# RadioBridge.net
KiCad netlist of a schematic drawn in EAGLE
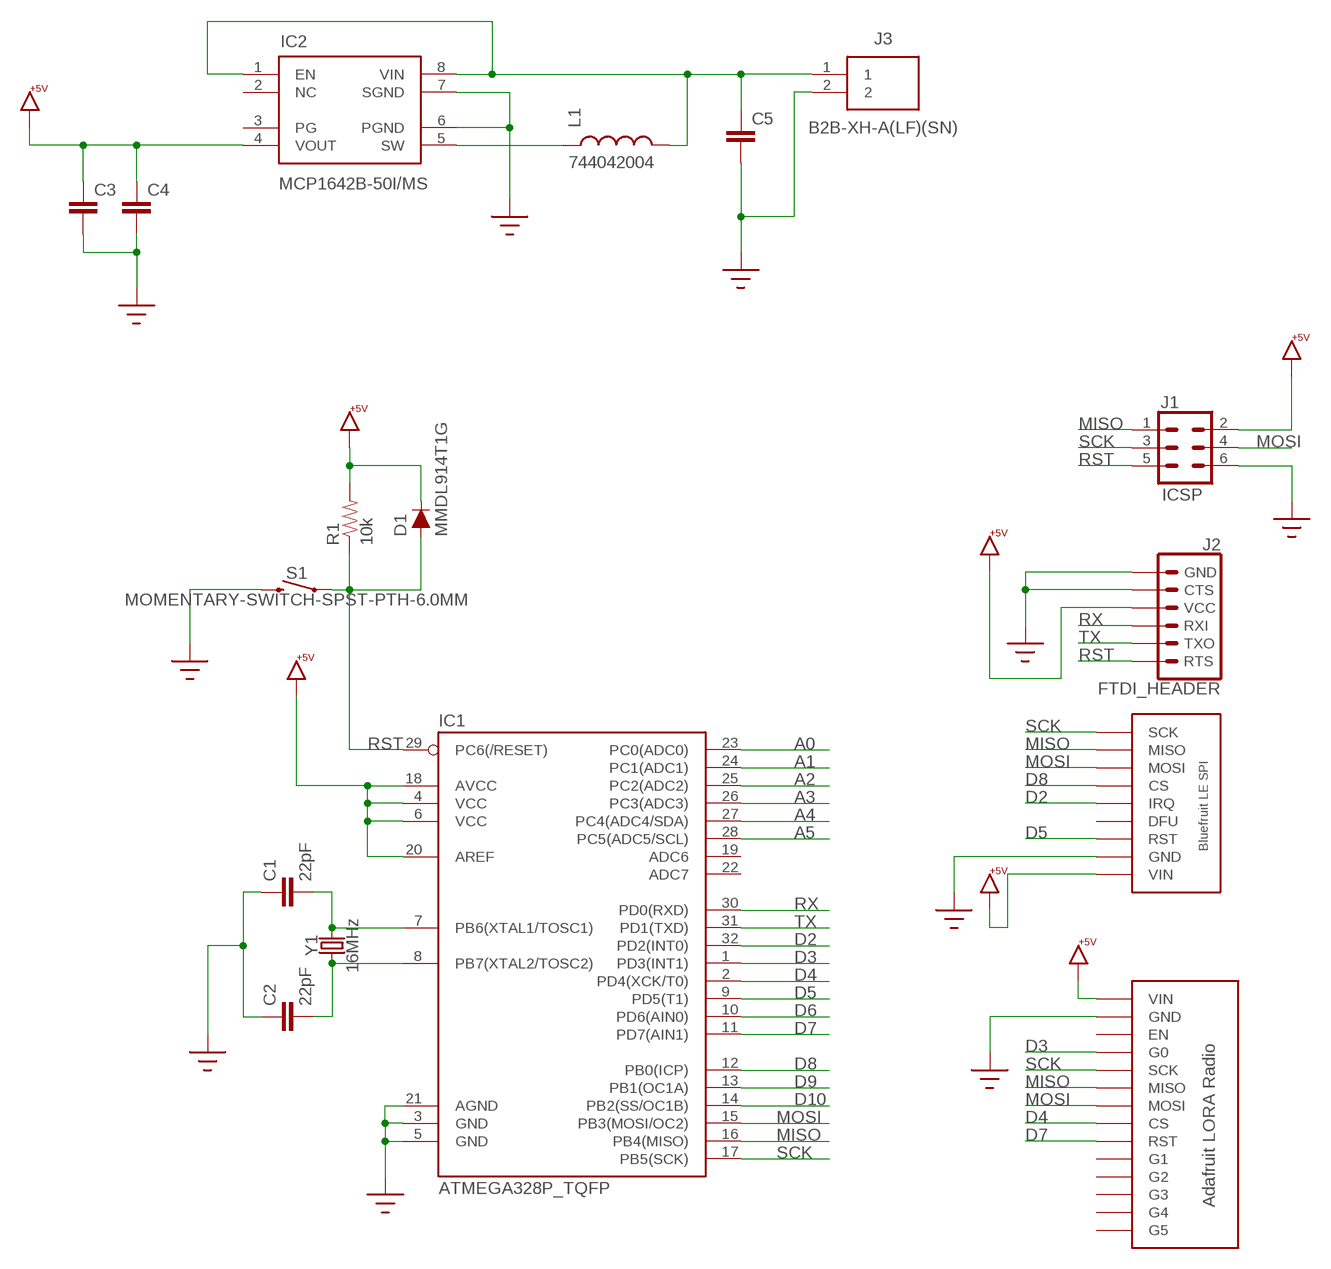
[diagram p0: schematic, sheet 1]

(export (version "E")
  (design (tool "Eeschema 10.0.6"))
  (components
    (comp (ref "C1")
      (value "22pF")
      (footprint "eagle-import:0603-CAP")
      (libsource (lib "eagle-import") (part "CAP0603-CAP"))
    )
    (comp (ref "C2")
      (value "22pF")
      (footprint "eagle-import:0603-CAP")
      (libsource (lib "eagle-import") (part "CAP0603-CAP"))
    )
    (comp (ref "C3")
      (value "CAP0805")
      (footprint "eagle-import:0805")
      (libsource (lib "eagle-import") (part "CAP0805"))
    )
    (comp (ref "C4")
      (value "CAP0805")
      (footprint "eagle-import:0805")
      (libsource (lib "eagle-import") (part "CAP0805"))
    )
    (comp (ref "C5")
      (value "CAP0805")
      (footprint "eagle-import:0805")
      (libsource (lib "eagle-import") (part "CAP0805"))
    )
    (comp (ref "D1")
      (value "MMDL914T1G")
      (footprint "eagle-import:SOD-323")
      (libsource (lib "eagle-import") (part "DIODE-BAS16J"))
    )
    (comp (ref "IC1")
      (value "ATMEGA328P_TQFP")
      (footprint "eagle-import:TQFP32-08")
      (libsource (lib "eagle-import") (part "ATMEGA328P_TQFP"))
    )
    (comp (ref "IC2")
      (value "MCP1642B-50I/MS")
      (footprint "eagle-import:MSOP8")
      (libsource (lib "eagle-import") (part "MCP1642B-50I/MS"))
    )
    (comp (ref "J1")
      (value "ICSP")
      (footprint "eagle-import:2X3")
      (libsource (lib "eagle-import") (part "CONN_03X22X3_SILK_MALE_PTH"))
    )
    (comp (ref "J2")
      (value "FTDI_HEADER")
      (footprint "eagle-import:1X06_LOCK")
      (libsource (lib "eagle-import") (part "6_PIN_SERIAL_TARGETLOCK"))
    )
    (comp (ref "J3")
      (value "B2B-XH-A(LF)(SN)")
      (footprint "eagle-import:SHDR2W64P0X250_1X2_740X575X700")
      (fields (field (name "RS_PART_NUMBER") "8201554"))
      (libsource (lib "eagle-import") (part "B2B-XH-A(LF)(SN)"))
    )
    (comp (ref "L1")
      (value "744042004")
      (footprint "eagle-import:1919(4848_METRIC)")
      (libsource (lib "eagle-import") (part "INDUCTOR"))
    )
    (comp (ref "R1")
      (value "10k")
      (footprint "eagle-import:0603-RES")
      (libsource (lib "eagle-import") (part "RESISTOR0603-RES"))
    )
    (comp (ref "S1")
      (value "MOMENTARY-SWITCH-SPST-PTH-6.0MM")
      (footprint "eagle-import:TACTILE_SWITCH_PTH_6.0MM")
      (libsource (lib "eagle-import") (part "MOMENTARY-SWITCH-SPST-PTH-6.0MM"))
    )
    (comp (ref "U$1")
      (value "BLUEFRUIT_LE_FRIEND_SPI")
      (footprint "eagle-import:BLUEFRUIT_LE_FRIEND_SPI")
      (libsource (lib "eagle-import") (part "BLUEFRUIT_LE_FRIEND_SPI"))
    )
    (comp (ref "U$2")
      (value "ADAFRUIT_LORA_RADIO")
      (footprint "eagle-import:ADAFRUIT_LORA_RADIO")
      (libsource (lib "eagle-import") (part "ADAFRUIT_LORA_RADIO"))
    )
    (comp (ref "Y1")
      (value "16MHz")
      (footprint "eagle-import:CRYSTAL-SMD-5X3.2-4PAD")
      (libsource (lib "eagle-import") (part "CRYSTAL-16MHZSMD-5X3.2"))
    )
  )
  (nets
    (net (code "1") (name "+5V") (class "Default")
      (node (ref "C3") (pin "1") (pinfunction "1_1") (pintype "passive"))
      (node (ref "C4") (pin "1") (pinfunction "1_1") (pintype "passive"))
      (node (ref "D1") (pin "C") (pinfunction "C_C") (pintype "passive"))
      (node (ref "IC1") (pin "18") (pinfunction "AVCC_18") (pintype "bidirectional"))
      (node (ref "IC1") (pin "20") (pinfunction "AREF_20") (pintype "bidirectional"))
      (node (ref "IC1") (pin "4") (pinfunction "VCC_4") (pintype "bidirectional"))
      (node (ref "IC1") (pin "6") (pinfunction "VCC_6") (pintype "bidirectional"))
      (node (ref "IC2") (pin "4") (pinfunction "VOUT_4") (pintype "bidirectional"))
      (node (ref "J1") (pin "2") (pinfunction "2_2") (pintype "bidirectional"))
      (node (ref "J2") (pin "4") (pinfunction "VCC_4") (pintype "passive"))
      (node (ref "R1") (pin "2") (pinfunction "2_2") (pintype "passive"))
      (node (ref "U$1") (pin "P$9") (pinfunction "VIN_P$9") (pintype "bidirectional"))
      (node (ref "U$2") (pin "P$1") (pinfunction "VIN_P$1") (pintype "bidirectional"))
    )
    (net (code "2") (name "/A0") (class "Default")
      (node (ref "IC1") (pin "23") (pinfunction "PC0(ADC0)_23") (pintype "bidirectional"))
    )
    (net (code "3") (name "/A1") (class "Default")
      (node (ref "IC1") (pin "24") (pinfunction "PC1(ADC1)_24") (pintype "bidirectional"))
    )
    (net (code "4") (name "/A2") (class "Default")
      (node (ref "IC1") (pin "25") (pinfunction "PC2(ADC2)_25") (pintype "bidirectional"))
    )
    (net (code "5") (name "/A3") (class "Default")
      (node (ref "IC1") (pin "26") (pinfunction "PC3(ADC3)_26") (pintype "bidirectional"))
    )
    (net (code "6") (name "/A4") (class "Default")
      (node (ref "IC1") (pin "27") (pinfunction "PC4(ADC4/SDA)_27") (pintype "bidirectional"))
    )
    (net (code "7") (name "/A5") (class "Default")
      (node (ref "IC1") (pin "28") (pinfunction "PC5(ADC5/SCL)_28") (pintype "bidirectional"))
    )
    (net (code "8") (name "/D2") (class "Default")
      (node (ref "IC1") (pin "32") (pinfunction "PD2(INT0)_32") (pintype "bidirectional"))
      (node (ref "U$1") (pin "P$5") (pinfunction "IRQ_P$5") (pintype "bidirectional"))
    )
    (net (code "9") (name "/D3") (class "Default")
      (node (ref "IC1") (pin "1") (pinfunction "PD3(INT1)_1") (pintype "bidirectional"))
      (node (ref "U$2") (pin "P$4") (pinfunction "G0_P$4") (pintype "bidirectional"))
    )
    (net (code "10") (name "/D4") (class "Default")
      (node (ref "IC1") (pin "2") (pinfunction "PD4(XCK/T0)_2") (pintype "bidirectional"))
      (node (ref "U$2") (pin "P$8") (pinfunction "CS_P$8") (pintype "bidirectional"))
    )
    (net (code "11") (name "/D5") (class "Default")
      (node (ref "IC1") (pin "9") (pinfunction "PD5(T1)_9") (pintype "bidirectional"))
      (node (ref "U$1") (pin "P$7") (pinfunction "RST_P$7") (pintype "bidirectional"))
    )
    (net (code "12") (name "/D6") (class "Default")
      (node (ref "IC1") (pin "10") (pinfunction "PD6(AIN0)_10") (pintype "bidirectional"))
    )
    (net (code "13") (name "/D7") (class "Default")
      (node (ref "IC1") (pin "11") (pinfunction "PD7(AIN1)_11") (pintype "bidirectional"))
      (node (ref "U$2") (pin "P$9") (pinfunction "RST_P$9") (pintype "bidirectional"))
    )
    (net (code "14") (name "/D8") (class "Default")
      (node (ref "IC1") (pin "12") (pinfunction "PB0(ICP)_12") (pintype "bidirectional"))
      (node (ref "U$1") (pin "P$4") (pinfunction "CS_P$4") (pintype "bidirectional"))
    )
    (net (code "15") (name "/D9") (class "Default")
      (node (ref "IC1") (pin "13") (pinfunction "PB1(OC1A)_13") (pintype "bidirectional"))
    )
    (net (code "16") (name "/D10") (class "Default")
      (node (ref "IC1") (pin "14") (pinfunction "PB2(SS/OC1B)_14") (pintype "bidirectional"))
    )
    (net (code "17") (name "/MISO") (class "Default")
      (node (ref "IC1") (pin "16") (pinfunction "PB4(MISO)_16") (pintype "bidirectional"))
      (node (ref "J1") (pin "1") (pinfunction "1_1") (pintype "bidirectional"))
      (node (ref "U$1") (pin "P$2") (pinfunction "MISO_P$2") (pintype "bidirectional"))
      (node (ref "U$2") (pin "P$6") (pinfunction "MISO_P$6") (pintype "bidirectional"))
    )
    (net (code "18") (name "/MOSI") (class "Default")
      (node (ref "IC1") (pin "15") (pinfunction "PB3(MOSI/OC2)_15") (pintype "bidirectional"))
      (node (ref "J1") (pin "4") (pinfunction "4_4") (pintype "bidirectional"))
      (node (ref "U$1") (pin "P$3") (pinfunction "MOSI_P$3") (pintype "bidirectional"))
      (node (ref "U$2") (pin "P$7") (pinfunction "MOSI_P$7") (pintype "bidirectional"))
    )
    (net (code "19") (name "/RST") (class "Default")
      (node (ref "D1") (pin "A") (pinfunction "A_A") (pintype "passive"))
      (node (ref "IC1") (pin "29") (pinfunction "PC6(/RESET)_29") (pintype "bidirectional"))
      (node (ref "J1") (pin "5") (pinfunction "5_5") (pintype "bidirectional"))
      (node (ref "J2") (pin "1") (pinfunction "RTS_1") (pintype "passive"))
      (node (ref "R1") (pin "1") (pinfunction "1_1") (pintype "passive"))
      (node (ref "S1") (pin "1") (pinfunction "1_1") (pintype "passive"))
    )
    (net (code "20") (name "/RX") (class "Default")
      (node (ref "IC1") (pin "30") (pinfunction "PD0(RXD)_30") (pintype "bidirectional"))
      (node (ref "J2") (pin "3") (pinfunction "RXI_3") (pintype "passive"))
    )
    (net (code "21") (name "/SCK") (class "Default")
      (node (ref "IC1") (pin "17") (pinfunction "PB5(SCK)_17") (pintype "bidirectional"))
      (node (ref "J1") (pin "3") (pinfunction "3_3") (pintype "bidirectional"))
      (node (ref "U$1") (pin "P$1") (pinfunction "SCK_P$1") (pintype "bidirectional"))
      (node (ref "U$2") (pin "P$5") (pinfunction "SCK_P$5") (pintype "bidirectional"))
    )
    (net (code "22") (name "/TX") (class "Default")
      (node (ref "IC1") (pin "31") (pinfunction "PD1(TXD)_31") (pintype "bidirectional"))
      (node (ref "J2") (pin "2") (pinfunction "TXO_2") (pintype "passive"))
    )
    (net (code "23") (name "GND") (class "Default")
      (node (ref "C1") (pin "1") (pinfunction "1_1") (pintype "passive"))
      (node (ref "C2") (pin "1") (pinfunction "1_1") (pintype "passive"))
      (node (ref "C3") (pin "2") (pinfunction "2_2") (pintype "passive"))
      (node (ref "C4") (pin "2") (pinfunction "2_2") (pintype "passive"))
      (node (ref "C5") (pin "2") (pinfunction "2_2") (pintype "passive"))
      (node (ref "IC1") (pin "21") (pinfunction "AGND_21") (pintype "bidirectional"))
      (node (ref "IC1") (pin "3") (pinfunction "GND_3") (pintype "bidirectional"))
      (node (ref "IC1") (pin "5") (pinfunction "GND_5") (pintype "bidirectional"))
      (node (ref "IC2") (pin "6") (pinfunction "PGND_6") (pintype "bidirectional"))
      (node (ref "IC2") (pin "7") (pinfunction "SGND_7") (pintype "bidirectional"))
      (node (ref "J1") (pin "6") (pinfunction "6_6") (pintype "bidirectional"))
      (node (ref "J2") (pin "5") (pinfunction "CTS_5") (pintype "passive"))
      (node (ref "J2") (pin "6") (pinfunction "GND_6") (pintype "passive"))
      (node (ref "J3") (pin "2") (pinfunction "2_2") (pintype "input"))
      (node (ref "S1") (pin "3") (pinfunction "2_3") (pintype "passive"))
      (node (ref "U$1") (pin "P$8") (pinfunction "GND_P$8") (pintype "bidirectional"))
      (node (ref "U$2") (pin "P$2") (pinfunction "GND_P$2") (pintype "bidirectional"))
    )
    (net (code "24") (name "Net-(IC1-PB6(XTAL1{slash}TOSC1))") (class "Default")
      (node (ref "C1") (pin "2") (pinfunction "2_2") (pintype "passive"))
      (node (ref "IC1") (pin "7") (pinfunction "PB6(XTAL1/TOSC1)_7") (pintype "bidirectional"))
      (node (ref "Y1") (pin "3") (pinfunction "2_3") (pintype "passive"))
    )
    (net (code "25") (name "Net-(IC1-PB7(XTAL2{slash}TOSC2))") (class "Default")
      (node (ref "C2") (pin "2") (pinfunction "2_2") (pintype "passive"))
      (node (ref "IC1") (pin "8") (pinfunction "PB7(XTAL2/TOSC2)_8") (pintype "bidirectional"))
      (node (ref "Y1") (pin "1") (pinfunction "1_1") (pintype "passive"))
    )
    (net (code "26") (name "Net-(IC2-EN)") (class "Default")
      (node (ref "C5") (pin "1") (pinfunction "1_1") (pintype "passive"))
      (node (ref "IC2") (pin "1") (pinfunction "EN_1") (pintype "bidirectional"))
      (node (ref "IC2") (pin "8") (pinfunction "VIN_8") (pintype "bidirectional"))
      (node (ref "J3") (pin "1") (pinfunction "1_1") (pintype "input"))
      (node (ref "L1") (pin "P$2") (pinfunction "2_P$2") (pintype "passive"))
    )
    (net (code "27") (name "Net-(IC2-SW)") (class "Default")
      (node (ref "IC2") (pin "5") (pinfunction "SW_5") (pintype "bidirectional"))
      (node (ref "L1") (pin "P$1") (pinfunction "1_P$1") (pintype "passive"))
    )
    (net (code "28") (name "unconnected-(IC1-ADC6-Pad19)") (class "Default")
      (node (ref "IC1") (pin "19") (pinfunction "ADC6_19") (pintype "bidirectional"))
    )
    (net (code "29") (name "unconnected-(IC1-ADC7-Pad22)") (class "Default")
      (node (ref "IC1") (pin "22") (pinfunction "ADC7_22") (pintype "bidirectional"))
    )
    (net (code "30") (name "unconnected-(IC2-NC-Pad2)") (class "Default")
      (node (ref "IC2") (pin "2") (pinfunction "NC_2") (pintype "bidirectional"))
    )
    (net (code "31") (name "unconnected-(IC2-PG-Pad3)") (class "Default")
      (node (ref "IC2") (pin "3") (pinfunction "PG_3") (pintype "bidirectional"))
    )
    (net (code "32") (name "unconnected-(U$1-DFU-PadP$6)") (class "Default")
      (node (ref "U$1") (pin "P$6") (pinfunction "DFU_P$6") (pintype "bidirectional"))
    )
    (net (code "33") (name "unconnected-(U$2-EN-PadP$3)") (class "Default")
      (node (ref "U$2") (pin "P$3") (pinfunction "EN_P$3") (pintype "bidirectional"))
    )
    (net (code "34") (name "unconnected-(U$2-G1-PadP$10)") (class "Default")
      (node (ref "U$2") (pin "P$10") (pinfunction "G1_P$10") (pintype "bidirectional"))
    )
    (net (code "35") (name "unconnected-(U$2-G2-PadP$11)") (class "Default")
      (node (ref "U$2") (pin "P$11") (pinfunction "G2_P$11") (pintype "bidirectional"))
    )
    (net (code "36") (name "unconnected-(U$2-G3-PadP$12)") (class "Default")
      (node (ref "U$2") (pin "P$12") (pinfunction "G3_P$12") (pintype "bidirectional"))
    )
    (net (code "37") (name "unconnected-(U$2-G4-PadP$13)") (class "Default")
      (node (ref "U$2") (pin "P$13") (pinfunction "G4_P$13") (pintype "bidirectional"))
    )
    (net (code "38") (name "unconnected-(U$2-G5-PadP$14)") (class "Default")
      (node (ref "U$2") (pin "P$14") (pinfunction "G5_P$14") (pintype "bidirectional"))
    )
  )
)
